# SH9_-_USB.net
KiCad netlist of a schematic drawn in Altium Designer
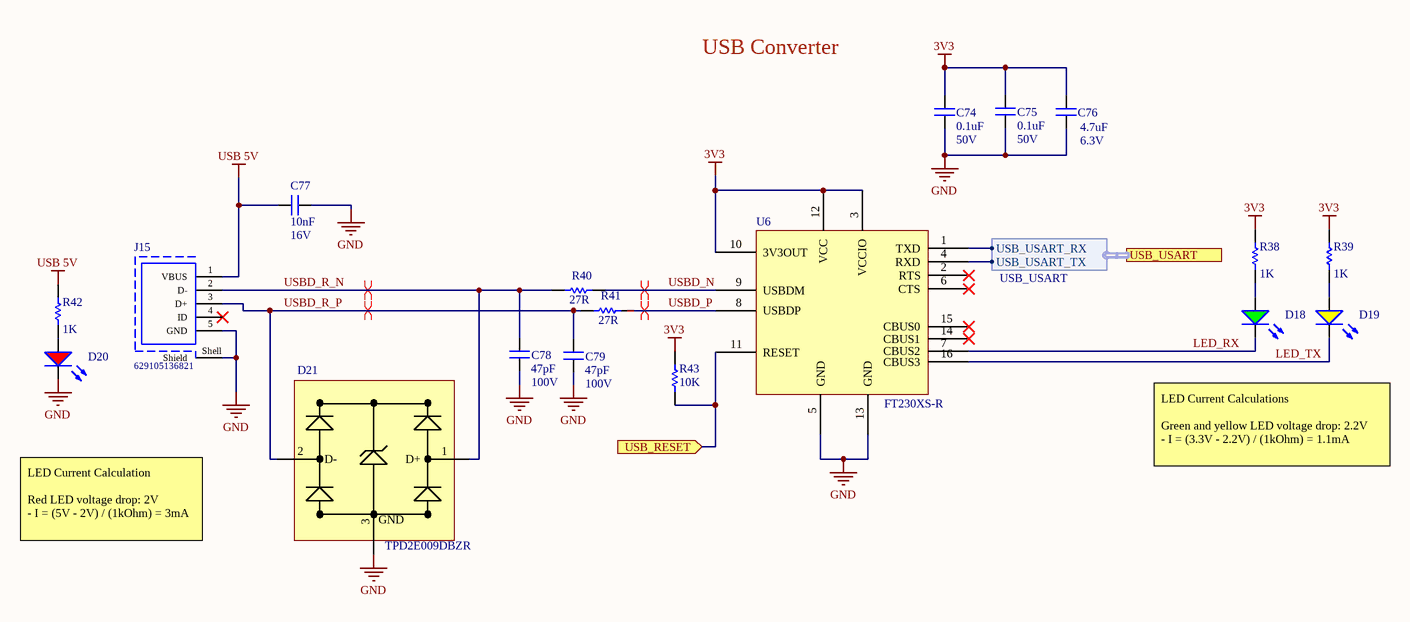
[diagram p0: SH9 - USB.SchDoc]

(export (version "E")
  (design (tool "Eeschema 10.0.6"))
  (components
    (comp (ref "C74")
      (value "0.1uF")
      (footprint "CAPC2012X140N")
      (description "CAP CER 0.1UF 50V X7R 0805")
      (fields
        (field (name "TOLERANCE") "10%")
        (field (name "VOLTAGE RATING") "50V")
        (field (name "Comment") "CAP_0.1uF_50V_0805")
      )
      (libsource (lib "UWRT_Schematic_Library_2020") (part "CAP_0.1uF_50V_0805"))
    )
    (comp (ref "C75")
      (value "0.1uF")
      (footprint "CAPC2012X140N")
      (description "CAP CER 0.1UF 50V X7R 0805")
      (fields
        (field (name "TOLERANCE") "10%")
        (field (name "VOLTAGE RATING") "50V")
        (field (name "Comment") "CAP_0.1uF_50V_0805")
      )
      (libsource (lib "UWRT_Schematic_Library_2020") (part "CAP_0.1uF_50V_0805"))
    )
    (comp (ref "C76")
      (value "4.7uF")
      (footprint "CAPC0603(1608)55_N")
      (description "CAP CER 4.7UF 6.3V X5R 0603")
      (fields (field (name "VOLTAGE RATING") "6.3V") (field (name "Comment") "CAP_4.7uF_0603"))
      (libsource (lib "UWRT_Schematic_Library_2020") (part "CAP_4.7uF_0603"))
    )
    (comp (ref "C77")
      (value "10nF")
      (footprint "CAPC0603(1608)55_N")
      (description "CAP CER 10000PF 16V X7R 0603")
      (fields (field (name "VOLTAGE RATING") "16V") (field (name "Comment") "CAP_10nF_0603"))
      (libsource (lib "UWRT_Schematic_Library_2020") (part "CAP_10nF_0603"))
    )
    (comp (ref "C78")
      (value "47pF")
      (footprint "CAPC1608X87N")
      (description "CAP CER 47PF 100V C0G/NP0 0603")
      (fields (field (name "VOLTAGE RATING") "100V") (field (name "Comment") "CAP_47pF_100V_0603"))
      (libsource (lib "UWRT_Schematic_Library_2020") (part "CAP_47pF_100V_0603"))
    )
    (comp (ref "C79")
      (value "47pF")
      (footprint "CAPC1608X87N")
      (description "CAP CER 47PF 100V C0G/NP0 0603")
      (fields (field (name "VOLTAGE RATING") "100V") (field (name "Comment") "CAP_47pF_100V_0603"))
      (libsource (lib "UWRT_Schematic_Library_2020") (part "CAP_47pF_100V_0603"))
    )
    (comp (ref "D18")
      (value "DIO_LED_G")
      (footprint "LED_0805_LINE")
      (description "LED GREEN DIFFUSED 0805 SMD")
      (libsource (lib "UWRT_Schematic_Library_2020") (part "DIO_LED_G"))
    )
    (comp (ref "D19")
      (value "DIO_LED_Y")
      (footprint "LED_0805_LINE")
      (description "LED YELLOW DIFFUSED 0805 SMD")
      (libsource (lib "UWRT_Schematic_Library_2020") (part "DIO_LED_Y"))
    )
    (comp (ref "D20")
      (value "DIO_LED_R")
      (footprint "LED_0805_LINE")
      (description "LED RED DIFFUSED 0805 SMD")
      (libsource (lib "UWRT_Schematic_Library_2020") (part "DIO_LED_R"))
    )
    (comp (ref "D21")
      (value "TVS_DIODE_USB_5.5V")
      (footprint "SOT23-3")
      (description "ESD Suppressor Diode Arrays 8KV 3-Pin SOT-23 T/R")
      (fields
        (field (name "MANUFACTURER") "Texas Instruments")
        (field (name "MANUFACTURER PART NUMBER") "TPD2E009DBZR")
      )
      (libsource (lib "UWRT_Schematic_Library_2020") (part "TVS_DIODE_USB_5.5V"))
    )
    (comp (ref "J15")
      (value "629105136821")
      (footprint "629105136821")
      (description "Micro USB 2.0 Type B Receptacle WR-COM, Horizontal, SMT, with Pads and Pegs")
      (fields (field (name "MANUFACTURER") "Wurth Elektronik") (field (name "PUBLISHER") "WurthElektronik"))
      (libsource (lib "UWRT_Schematic_Library_2020") (part "WE 629105136821"))
    )
    (comp (ref "R38")
      (value "1K")
      (footprint "RESC0603(1608)_N")
      (description "RES SMD 1K OHM 5% 1/10W 0603")
      (fields (field (name "TOLERANCE") "5%") (field (name "Comment") "RES_1K_0603"))
      (libsource (lib "UWRT_Schematic_Library_2020") (part "RES_1K_0603"))
    )
    (comp (ref "R39")
      (value "1K")
      (footprint "RESC0603(1608)_N")
      (description "RES SMD 1K OHM 5% 1/10W 0603")
      (fields (field (name "TOLERANCE") "5%") (field (name "Comment") "RES_1K_0603"))
      (libsource (lib "UWRT_Schematic_Library_2020") (part "RES_1K_0603"))
    )
    (comp (ref "R40")
      (value "RES_27R_0603")
      (footprint "RESC0603(1608)_N")
      (description "RES SMD 27 OHM 5% 1/10W 0603")
      (fields
        (field (name "MANUFACTURER") "Yageo")
        (field (name "MANUFACTURER PART NUMBER") "RC0603JR-0727RL")
        (field (name "RESISTANCE") "27R")
      )
      (libsource (lib "UWRT_Schematic_Library_2020") (part "RES_27R_0603"))
    )
    (comp (ref "R41")
      (value "RES_27R_0603")
      (footprint "RESC0603(1608)_N")
      (description "RES SMD 27 OHM 5% 1/10W 0603")
      (fields
        (field (name "MANUFACTURER") "Yageo")
        (field (name "MANUFACTURER PART NUMBER") "RC0603JR-0727RL")
        (field (name "RESISTANCE") "27R")
      )
      (libsource (lib "UWRT_Schematic_Library_2020") (part "RES_27R_0603"))
    )
    (comp (ref "R42")
      (value "1K")
      (footprint "RESC0603(1608)_N")
      (description "RES SMD 1K OHM 5% 1/10W 0603")
      (fields (field (name "TOLERANCE") "5%") (field (name "Comment") "RES_1K_0603"))
      (libsource (lib "UWRT_Schematic_Library_2020") (part "RES_1K_0603"))
    )
    (comp (ref "R43")
      (value "10K")
      (footprint "RESC0603(1608)_N")
      (description "RES SMD 10K OHM 5% 1/10W 0603")
      (fields (field (name "TOLERANCE") "5%") (field (name "Comment") "RES_10K_0603"))
      (libsource (lib "UWRT_Schematic_Library_2020") (part "RES_10K_0603"))
    )
    (comp (ref "U6")
      (value "IC_USB_TRANSCEIVER")
      (footprint "SSOP16-0.635-5X4MM")
      (fields (field (name "MANUFACTURER PART NUMBER 1") "FT230XS-R"))
      (libsource (lib "UWRT_Schematic_Library_2020") (part "IC_USB_TRANSCEIVER"))
    )
  )
  (nets
    (net (code "2") (name "/LED_RX") (class "Default")
      (node (ref "D18") (pin "2") (pinfunction "K_2") (pintype "passive"))
      (node (ref "U6") (pin "7") (pinfunction "CBUS2_7") (pintype "passive"))
    )
    (net (code "3") (name "/LED_TX") (class "Default")
      (node (ref "D19") (pin "2") (pinfunction "K_2") (pintype "passive"))
      (node (ref "U6") (pin "16") (pinfunction "CBUS3_16") (pintype "passive"))
    )
    (net (code "4") (name "/USBD_N") (class "Default")
      (node (ref "R40") (pin "2") (pinfunction "2_2") (pintype "passive"))
      (node (ref "U6") (pin "9") (pinfunction "USBDM_9") (pintype "passive"))
    )
    (net (code "5") (name "/USBD_P") (class "Default")
      (node (ref "R41") (pin "2") (pinfunction "2_2") (pintype "passive"))
      (node (ref "U6") (pin "8") (pinfunction "USBDP_8") (pintype "passive"))
    )
    (net (code "6") (name "/USBD_R_N") (class "Default")
      (node (ref "C78") (pin "2") (pinfunction "2_2") (pintype "passive"))
      (node (ref "D21") (pin "1") (pinfunction "D+_1") (pintype "passive"))
      (node (ref "J15") (pin "2") (pinfunction "D-_2") (pintype "passive"))
      (node (ref "R40") (pin "1") (pinfunction "1_1") (pintype "passive"))
    )
    (net (code "7") (name "/USBD_R_P") (class "Default")
      (node (ref "C79") (pin "1") (pinfunction "1_1") (pintype "passive"))
      (node (ref "D21") (pin "2") (pinfunction "D-_2") (pintype "passive"))
      (node (ref "J15") (pin "3") (pinfunction "D+_3") (pintype "passive"))
      (node (ref "R41") (pin "1") (pinfunction "1_1") (pintype "passive"))
    )
    (net (code "8") (name "/USB_RESET") (class "Default")
      (node (ref "R43") (pin "1") (pinfunction "1_1") (pintype "passive"))
      (node (ref "U6") (pin "11") (pinfunction "RESET_11") (pintype "passive"))
    )
    (net (code "9") (name "/USB_USART_RX") (class "Default")
      (node (ref "U6") (pin "1") (pinfunction "TXD_1") (pintype "passive"))
    )
    (net (code "10") (name "/USB_USART_TX") (class "Default")
      (node (ref "U6") (pin "4") (pinfunction "RXD_4") (pintype "passive"))
    )
    (net (code "12") (name "3V3") (class "Default")
      (node (ref "C74") (pin "2") (pinfunction "2_2") (pintype "passive"))
      (node (ref "C75") (pin "2") (pinfunction "2_2") (pintype "passive"))
      (node (ref "C76") (pin "1") (pinfunction "1_1") (pintype "passive"))
      (node (ref "R38") (pin "2") (pinfunction "2_2") (pintype "passive"))
      (node (ref "R39") (pin "2") (pinfunction "2_2") (pintype "passive"))
      (node (ref "R43") (pin "2") (pinfunction "2_2") (pintype "passive"))
      (node (ref "U6") (pin "10") (pinfunction "3V3OUT_10") (pintype "passive"))
      (node (ref "U6") (pin "12") (pinfunction "VCC_12") (pintype "passive"))
      (node (ref "U6") (pin "3") (pinfunction "VCCIO_3") (pintype "passive"))
    )
    (net (code "13") (name "GND") (class "Default")
      (node (ref "C74") (pin "1") (pinfunction "1_1") (pintype "passive"))
      (node (ref "C75") (pin "1") (pinfunction "1_1") (pintype "passive"))
      (node (ref "C76") (pin "2") (pinfunction "2_2") (pintype "passive"))
      (node (ref "C77") (pin "2") (pinfunction "2_2") (pintype "passive"))
      (node (ref "C78") (pin "1") (pinfunction "1_1") (pintype "passive"))
      (node (ref "C79") (pin "2") (pinfunction "2_2") (pintype "passive"))
      (node (ref "D20") (pin "2") (pinfunction "K_2") (pintype "passive"))
      (node (ref "D21") (pin "3") (pinfunction "GND_3") (pintype "passive"))
      (node (ref "J15") (pin "5") (pinfunction "GND_5") (pintype "passive"))
      (node (ref "J15") (pin "Shell") (pinfunction "Shield_Shell") (pintype "passive"))
      (node (ref "U6") (pin "13") (pinfunction "GND_13") (pintype "passive"))
      (node (ref "U6") (pin "5") (pinfunction "GND_5") (pintype "passive"))
    )
    (net (code "14") (name "Net-(D18-A)") (class "Default")
      (node (ref "D18") (pin "1") (pinfunction "A_1") (pintype "passive"))
      (node (ref "R38") (pin "1") (pinfunction "1_1") (pintype "passive"))
    )
    (net (code "15") (name "Net-(D19-A)") (class "Default")
      (node (ref "D19") (pin "1") (pinfunction "A_1") (pintype "passive"))
      (node (ref "R39") (pin "1") (pinfunction "1_1") (pintype "passive"))
    )
    (net (code "16") (name "Net-(D20-A)") (class "Default")
      (node (ref "D20") (pin "1") (pinfunction "A_1") (pintype "passive"))
      (node (ref "R42") (pin "1") (pinfunction "1_1") (pintype "passive"))
    )
    (net (code "17") (name "USB 5V") (class "Default")
      (node (ref "C77") (pin "1") (pinfunction "1_1") (pintype "passive"))
      (node (ref "J15") (pin "1") (pinfunction "VBUS_1") (pintype "passive"))
      (node (ref "R42") (pin "2") (pinfunction "2_2") (pintype "passive"))
    )
    (net (code "18") (name "unconnected-(J15-ID-Pad4)") (class "Default")
      (node (ref "J15") (pin "4") (pinfunction "ID_4") (pintype "passive+no_connect"))
    )
    (net (code "19") (name "unconnected-(U6-CBUS0-Pad15)") (class "Default")
      (node (ref "U6") (pin "15") (pinfunction "CBUS0_15") (pintype "passive+no_connect"))
    )
    (net (code "20") (name "unconnected-(U6-CBUS1-Pad14)") (class "Default")
      (node (ref "U6") (pin "14") (pinfunction "CBUS1_14") (pintype "passive+no_connect"))
    )
    (net (code "21") (name "unconnected-(U6-CTS-Pad6)") (class "Default")
      (node (ref "U6") (pin "6") (pinfunction "CTS_6") (pintype "passive+no_connect"))
    )
    (net (code "22") (name "unconnected-(U6-RTS-Pad2)") (class "Default")
      (node (ref "U6") (pin "2") (pinfunction "RTS_2") (pintype "passive+no_connect"))
    )
  )
)
